# DM0260_Power.net
KiCad netlist of a schematic drawn in Altium Designer
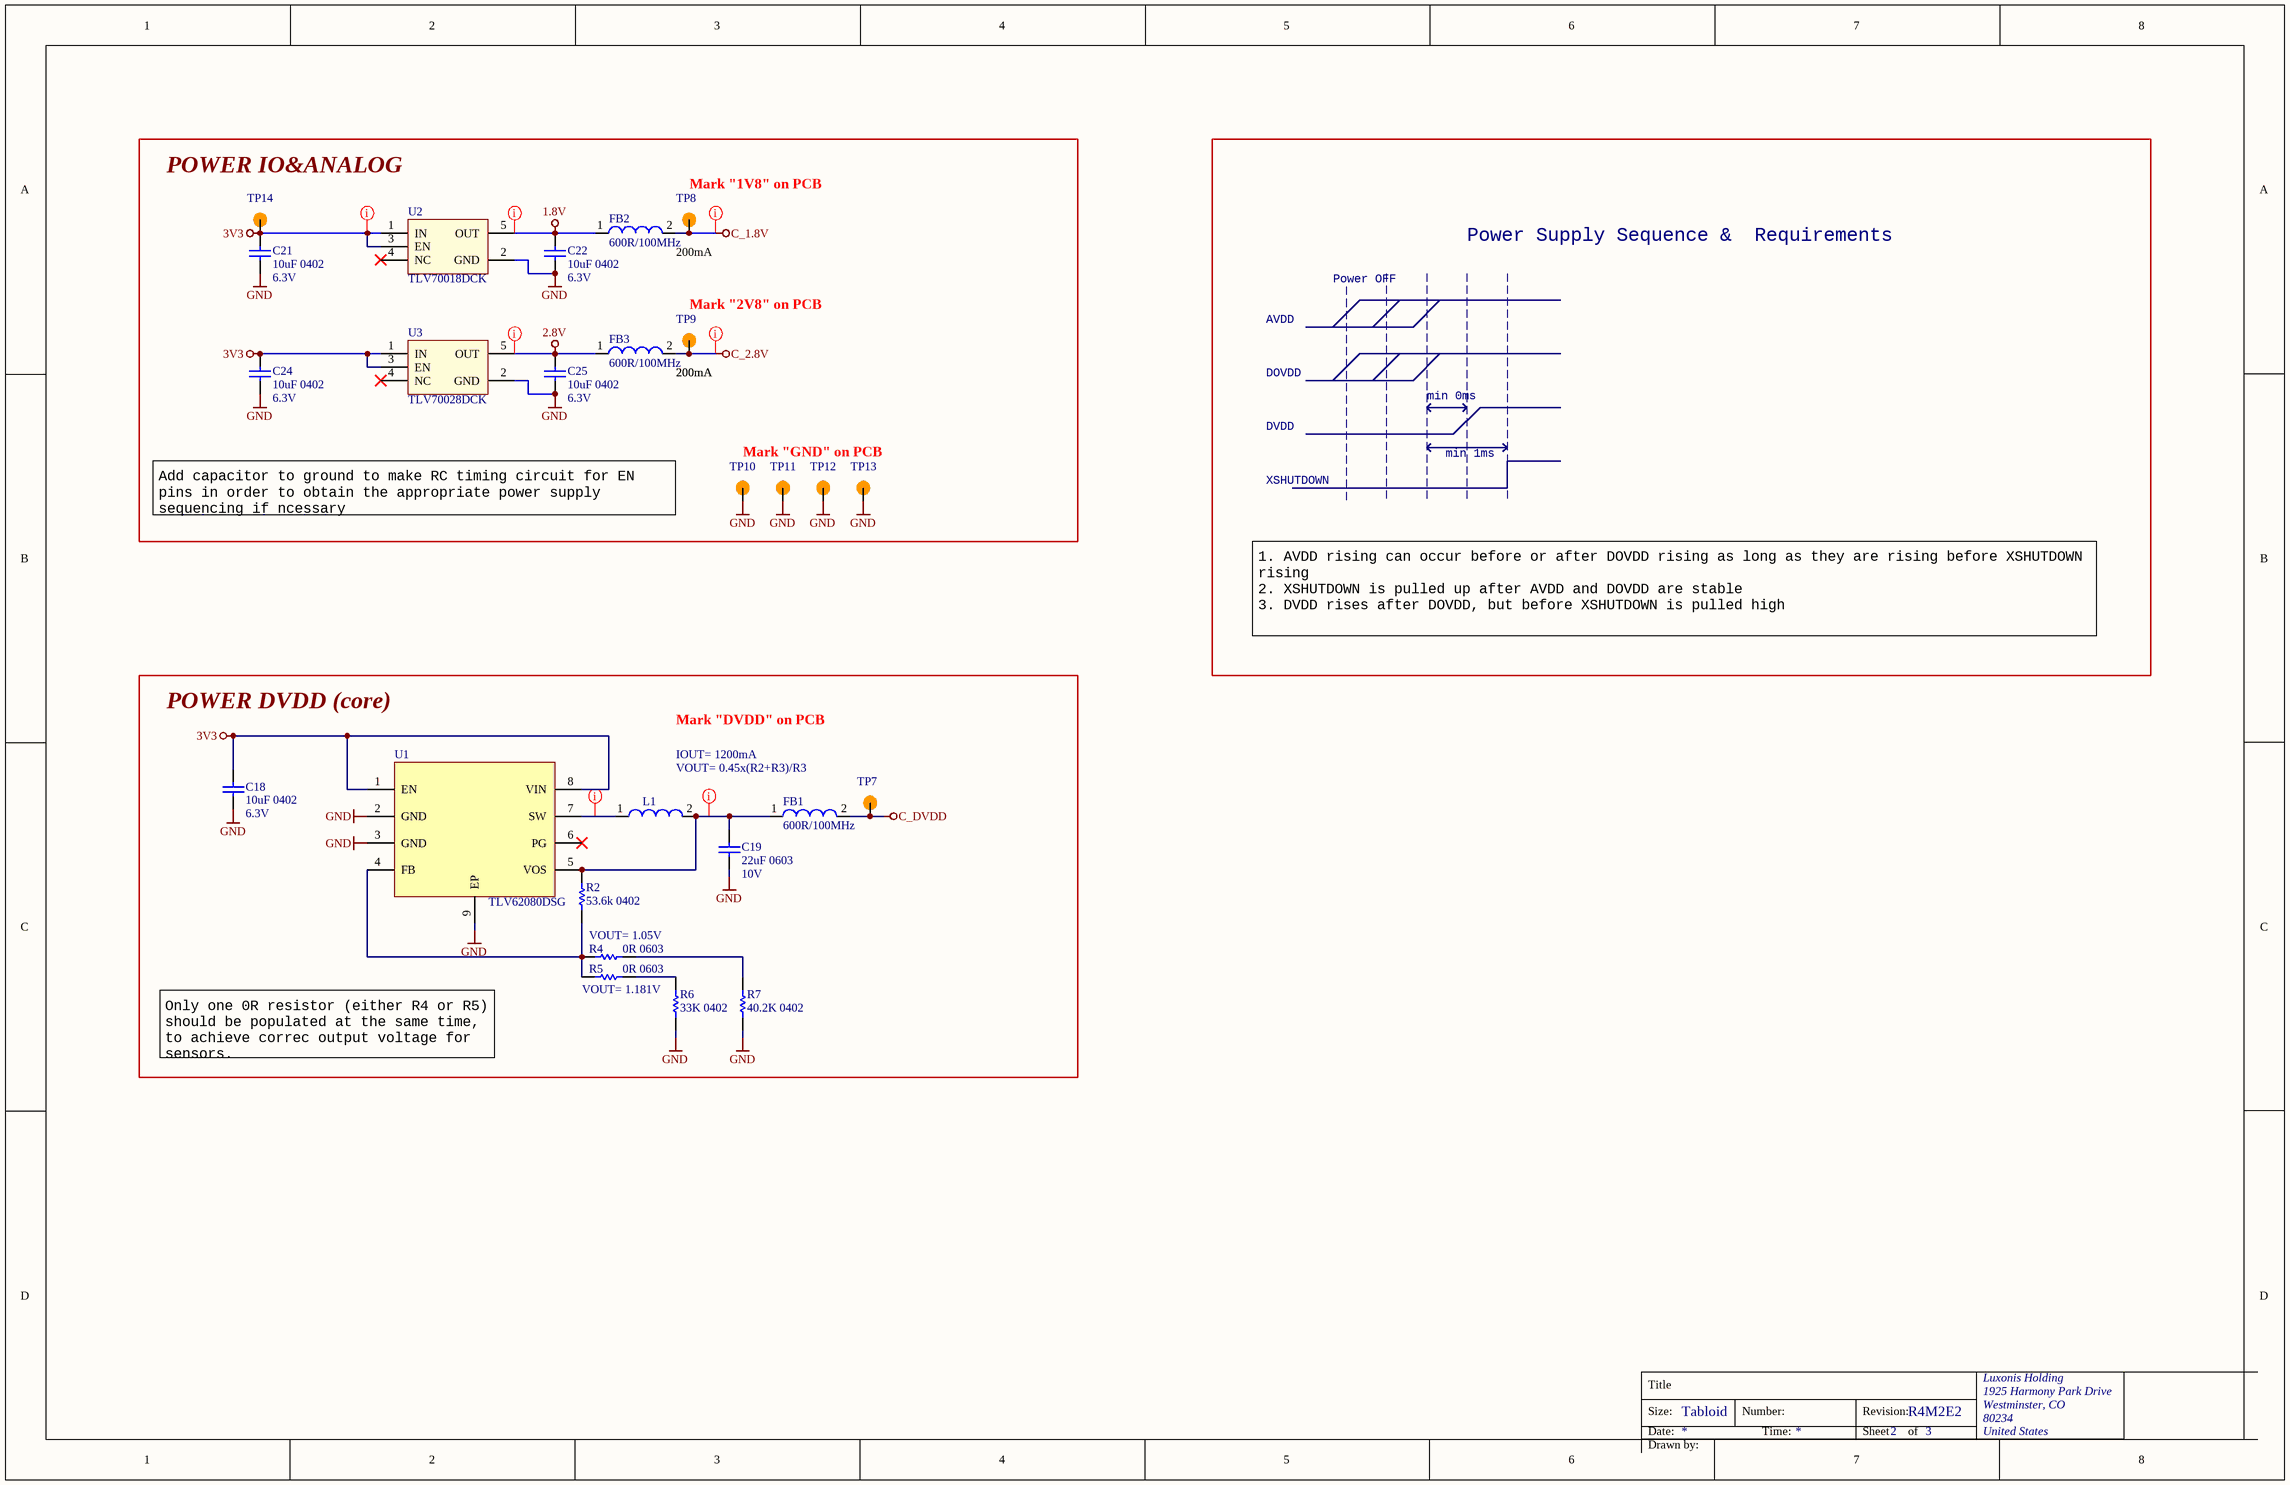
[diagram p0: DM0260_Power.SchDoc]

(export (version "E")
  (design (tool "Eeschema 10.0.6"))
  (components
    (comp (ref "C18")
      (value "10uF 0402")
      (footprint "CAP_Altium_Vault_Generic:CAPC0402(1005)70_L")
      (description "CAP CER 10UF 6.3V X5R 0402 20%")
      (fields (field (name "TOLERANCE") "20%") (field (name "VOLTAGE RATING") "6.3V"))
      (libsource (lib "LuxonisMaster") (part "GRM155R60J106ME15D"))
    )
    (comp (ref "C19")
      (value "22uF 0603")
      (footprint "CAP_Altium_Vault_Generic:CAPC0603(1608)100_L")
      (description "CAP CER 22UF 10V X5R 0603 20%")
      (fields (field (name "TOLERANCE") "20%") (field (name "VOLTAGE RATING") "10V"))
      (libsource (lib "LuxonisMaster") (part "GRM188R61A226ME15D"))
    )
    (comp (ref "C21")
      (value "10uF 0402")
      (footprint "CAP_Altium_Vault_Generic:CAPC0402(1005)70_N")
      (description "CAP CER 10UF 6.3V X5R 0402 20%")
      (fields (field (name "TOLERANCE") "20%") (field (name "VOLTAGE RATING") "6.3V"))
      (libsource (lib "LuxonisMaster") (part "GRM155R60J106ME15D"))
    )
    (comp (ref "C22")
      (value "10uF 0402")
      (footprint "CAP_Altium_Vault_Generic:CAPC0402(1005)70_N")
      (description "CAP CER 10UF 6.3V X5R 0402 20%")
      (fields (field (name "TOLERANCE") "20%") (field (name "VOLTAGE RATING") "6.3V"))
      (libsource (lib "LuxonisMaster") (part "GRM155R60J106ME15D"))
    )
    (comp (ref "C24")
      (value "10uF 0402")
      (footprint "CAP_Altium_Vault_Generic:CAPC0402(1005)70_N")
      (description "CAP CER 10UF 6.3V X5R 0402 20%")
      (fields (field (name "TOLERANCE") "20%") (field (name "VOLTAGE RATING") "6.3V"))
      (libsource (lib "LuxonisMaster") (part "GRM155R60J106ME15D"))
    )
    (comp (ref "C25")
      (value "10uF 0402")
      (footprint "CAP_Altium_Vault_Generic:CAPC0402(1005)70_N")
      (description "CAP CER 10UF 6.3V X5R 0402 20%")
      (fields (field (name "TOLERANCE") "20%") (field (name "VOLTAGE RATING") "6.3V"))
      (libsource (lib "LuxonisMaster") (part "GRM155R60J106ME15D"))
    )
    (comp (ref "FB1")
      (value "600R/100MHz")
      (footprint "LuxonisMaster:2508056017Y2")
      (description "FERRITE BEAD, 0.1OHM, 2A, 0805, 600R/100MHz")
      (fields (field (name "TOLERANCE") "25%"))
      (libsource (lib "LuxonisMaster") (part "2508056017Y2"))
    )
    (comp (ref "FB2")
      (value "600R/100MHz")
      (footprint "LuxonisMaster:2508056017Y2")
      (description "FERRITE BEAD, 0.1OHM, 2A, 0805, 600R/100MHz")
      (fields (field (name "TOLERANCE") "25%"))
      (libsource (lib "LuxonisMaster") (part "2508056017Y2"))
    )
    (comp (ref "FB3")
      (value "600R/100MHz")
      (footprint "LuxonisMaster:2508056017Y2")
      (description "FERRITE BEAD, 0.1OHM, 2A, 0805, 600R/100MHz")
      (fields (field (name "TOLERANCE") "25%"))
      (libsource (lib "LuxonisMaster") (part "2508056017Y2"))
    )
    (comp (ref "L1")
      (value "1uH, 3.2A, 20%")
      (footprint "LuxonisMaster:DFE252012P-1R0M=P2")
      (description "FIXED IND 1UH 3.2A 42 MOHM SMD")
      (fields
        (field (name "MANUFACTURER") "Murata")
        (field (name "MANUFACTURER PART NUMBER") "DFE252012P-1R0M=P2")
      )
      (libsource (lib "LuxonisMaster") (part "DFE252012P-1R0M=P2"))
    )
    (comp (ref "R2")
      (value "53.6k 0402")
      (footprint "RES_Altium_Vault_Generic:RESC0402(1005)_L")
      (description "RES SMD 53.6K OHM 1% 1/16W 0402")
      (fields (field (name "TOLERANCE") "1%"))
      (libsource (lib "LuxonisMaster") (part "CRCW040253K6FKED"))
    )
    (comp (ref "R4")
      (value "0R 0603")
      (footprint "RES_Altium_Vault_Generic:RESC0603(1608)_L")
      (description "RES SMD 0.0R OHM 1% 1/10W 0603")
      (fields (field (name "TOLERANCE") "5%"))
      (libsource (lib "LuxonisMaster") (part "CRCW06030000Z0EA"))
    )
    (comp (ref "R5")
      (value "0R 0603")
      (footprint "RES_Altium_Vault_Generic:RESC0603(1608)_L")
      (description "RES SMD 0.0R OHM 1% 1/10W 0603")
      (fields (field (name "TOLERANCE") "5%"))
      (libsource (lib "LuxonisMaster") (part "CRCW06030000Z0EA"))
    )
    (comp (ref "R6")
      (value "33K 0402")
      (footprint "RES_Altium_Vault_Generic:RESC0402(1005)_L")
      (description "RES SMD 33K OHM 1% 1/16W 0402")
      (fields (field (name "TOLERANCE") "1%"))
      (libsource (lib "LuxonisMaster") (part "CRCW040233K0FKED"))
    )
    (comp (ref "R7")
      (value "40.2K 0402")
      (footprint "RES_Altium_Vault_Generic:RESC0402(1005)_L")
      (description "RES SMD 40.2K OHM 1% 1/16W 0402")
      (fields (field (name "TOLERANCE") "1%"))
      (libsource (lib "LuxonisMaster") (part "RC0402FR-0740K2L"))
    )
    (comp (ref "TP7")
      (value "TP100_150_NS")
      (footprint "LuxonisMaster:TP100_150_NS")
      (libsource (lib "LuxonisMaster") (part "TEST_POINT"))
    )
    (comp (ref "TP8")
      (value "TP100_150_NS")
      (footprint "LuxonisMaster:TP100_150_NS")
      (libsource (lib "LuxonisMaster") (part "TEST_POINT"))
    )
    (comp (ref "TP9")
      (value "TP100_150_NS")
      (footprint "LuxonisMaster:TP100_150_NS")
      (libsource (lib "LuxonisMaster") (part "TEST_POINT"))
    )
    (comp (ref "TP10")
      (value "TP100_150_NS")
      (footprint "LuxonisMaster:TP100_150_NS")
      (libsource (lib "LuxonisMaster") (part "TEST_POINT"))
    )
    (comp (ref "TP11")
      (value "TP100_150_NS")
      (footprint "LuxonisMaster:TP100_150_NS")
      (libsource (lib "LuxonisMaster") (part "TEST_POINT"))
    )
    (comp (ref "TP12")
      (value "TP100_150_NS")
      (footprint "LuxonisMaster:TP100_150_NS")
      (libsource (lib "LuxonisMaster") (part "TEST_POINT"))
    )
    (comp (ref "TP13")
      (value "TP100_150_NS")
      (footprint "LuxonisMaster:TP100_150_NS")
      (libsource (lib "LuxonisMaster") (part "TEST_POINT"))
    )
    (comp (ref "TP14")
      (value "TP100_150_NS")
      (footprint "LuxonisMaster:TP100_150_NS")
      (libsource (lib "LuxonisMaster") (part "TEST_POINT"))
    )
    (comp (ref "U1")
      (value "TLV62080DSG")
      (footprint "LuxonisMaster:TLV62080DSG")
      (description "IC REG BUCK ADJ 1.2A SYNC 8WSON")
      (libsource (lib "LuxonisMaster") (part "TLV62080DSG"))
    )
    (comp (ref "U2")
      (value "TLV70018DCK")
      (footprint "LuxonisMaster:TLV70018DCK")
      (description "IC REG LINEAR 1.8V 200MA SC70-5 Linear Voltage Regulator IC  1 Output  200mA SC-70-5")
      (libsource (lib "LuxonisMaster") (part "TLV70018DCK"))
    )
    (comp (ref "U3")
      (value "TLV70028DCK")
      (footprint "LuxonisMaster:TLV70028DCK")
      (description "IC REG LINEAR 2.8V 200MA SC70-5 Linear Voltage Regulator IC  1 Output  200mA SC-70-5")
      (libsource (lib "LuxonisMaster") (part "TLV70028DCK"))
    )
  )
  (nets
    (net (code "1") (name "1.8V") (class "Default")
      (node (ref "C22") (pin "2") (pinfunction "2_2") (pintype "passive"))
      (node (ref "FB2") (pin "1") (pinfunction "1_1") (pintype "passive"))
      (node (ref "U2") (pin "5") (pinfunction "OUT_5") (pintype "passive"))
    )
    (net (code "2") (name "2.8V") (class "Default")
      (node (ref "C25") (pin "2") (pinfunction "2_2") (pintype "passive"))
      (node (ref "FB3") (pin "1") (pinfunction "1_1") (pintype "passive"))
      (node (ref "U3") (pin "5") (pinfunction "OUT_5") (pintype "passive"))
    )
    (net (code "3") (name "3V3") (class "Default")
      (node (ref "C18") (pin "2") (pinfunction "2_2") (pintype "passive"))
      (node (ref "C21") (pin "2") (pinfunction "2_2") (pintype "passive"))
      (node (ref "C24") (pin "2") (pinfunction "2_2") (pintype "passive"))
      (node (ref "TP14") (pin "1") (pintype "passive"))
      (node (ref "U1") (pin "1") (pinfunction "EN_1") (pintype "passive"))
      (node (ref "U1") (pin "8") (pinfunction "VIN_8") (pintype "passive"))
      (node (ref "U2") (pin "1") (pinfunction "IN_1") (pintype "passive"))
      (node (ref "U2") (pin "3") (pinfunction "EN_3") (pintype "passive"))
      (node (ref "U3") (pin "1") (pinfunction "IN_1") (pintype "passive"))
      (node (ref "U3") (pin "3") (pinfunction "EN_3") (pintype "passive"))
    )
    (net (code "4") (name "C_1.8V") (class "Default")
      (node (ref "FB2") (pin "2") (pinfunction "2_2") (pintype "passive"))
      (node (ref "TP8") (pin "1") (pintype "passive"))
    )
    (net (code "5") (name "C_2.8V") (class "Default")
      (node (ref "FB3") (pin "2") (pinfunction "2_2") (pintype "passive"))
      (node (ref "TP9") (pin "1") (pintype "passive"))
    )
    (net (code "6") (name "C_DVDD") (class "Default")
      (node (ref "FB1") (pin "2") (pinfunction "2_2") (pintype "passive"))
      (node (ref "TP7") (pin "1") (pintype "passive"))
    )
    (net (code "7") (name "GND") (class "Default")
      (node (ref "C18") (pin "1") (pinfunction "1_1") (pintype "passive"))
      (node (ref "C19") (pin "1") (pinfunction "1_1") (pintype "passive"))
      (node (ref "C21") (pin "1") (pinfunction "1_1") (pintype "passive"))
      (node (ref "C22") (pin "1") (pinfunction "1_1") (pintype "passive"))
      (node (ref "C24") (pin "1") (pinfunction "1_1") (pintype "passive"))
      (node (ref "C25") (pin "1") (pinfunction "1_1") (pintype "passive"))
      (node (ref "R6") (pin "1") (pinfunction "1_1") (pintype "passive"))
      (node (ref "R7") (pin "1") (pinfunction "1_1") (pintype "passive"))
      (node (ref "TP10") (pin "1") (pintype "passive"))
      (node (ref "TP11") (pin "1") (pintype "passive"))
      (node (ref "TP12") (pin "1") (pintype "passive"))
      (node (ref "TP13") (pin "1") (pintype "passive"))
      (node (ref "U1") (pin "2") (pinfunction "GND_2") (pintype "passive"))
      (node (ref "U1") (pin "3") (pinfunction "GND_3") (pintype "passive"))
      (node (ref "U1") (pin "9") (pinfunction "EP_9") (pintype "passive"))
      (node (ref "U2") (pin "2") (pinfunction "GND_2") (pintype "passive"))
      (node (ref "U3") (pin "2") (pinfunction "GND_2") (pintype "passive"))
    )
    (net (code "8") (name "Net-(R4-Pad2)") (class "Default")
      (node (ref "R4") (pin "2") (pinfunction "2_2") (pintype "passive"))
      (node (ref "R7") (pin "2") (pinfunction "2_2") (pintype "passive"))
    )
    (net (code "9") (name "Net-(R5-Pad2)") (class "Default")
      (node (ref "R5") (pin "2") (pinfunction "2_2") (pintype "passive"))
      (node (ref "R6") (pin "2") (pinfunction "2_2") (pintype "passive"))
    )
    (net (code "10") (name "Net-(U1-FB)") (class "Default")
      (node (ref "R2") (pin "1") (pinfunction "1_1") (pintype "passive"))
      (node (ref "R4") (pin "1") (pinfunction "1_1") (pintype "passive"))
      (node (ref "R5") (pin "1") (pinfunction "1_1") (pintype "passive"))
      (node (ref "U1") (pin "4") (pinfunction "FB_4") (pintype "passive"))
    )
    (net (code "11") (name "Net-(U1-SW)") (class "Default")
      (node (ref "L1") (pin "1") (pinfunction "1_1") (pintype "passive"))
      (node (ref "U1") (pin "7") (pinfunction "SW_7") (pintype "passive"))
    )
    (net (code "12") (name "Net-(U1-VOS)") (class "Default")
      (node (ref "C19") (pin "2") (pinfunction "2_2") (pintype "passive"))
      (node (ref "FB1") (pin "1") (pinfunction "1_1") (pintype "passive"))
      (node (ref "L1") (pin "2") (pinfunction "2_2") (pintype "passive"))
      (node (ref "R2") (pin "2") (pinfunction "2_2") (pintype "passive"))
      (node (ref "U1") (pin "5") (pinfunction "VOS_5") (pintype "passive"))
    )
    (net (code "13") (name "unconnected-(U1-PG-Pad6)") (class "Default")
      (node (ref "U1") (pin "6") (pinfunction "PG_6") (pintype "passive+no_connect"))
    )
    (net (code "14") (name "unconnected-(U2-NC-Pad4)") (class "Default")
      (node (ref "U2") (pin "4") (pinfunction "NC_4") (pintype "passive+no_connect"))
    )
    (net (code "15") (name "unconnected-(U3-NC-Pad4)") (class "Default")
      (node (ref "U3") (pin "4") (pinfunction "NC_4") (pintype "passive+no_connect"))
    )
  )
)
